# Rocky_Switch_Shield_v2.net
KiCad netlist of a schematic drawn in EAGLE
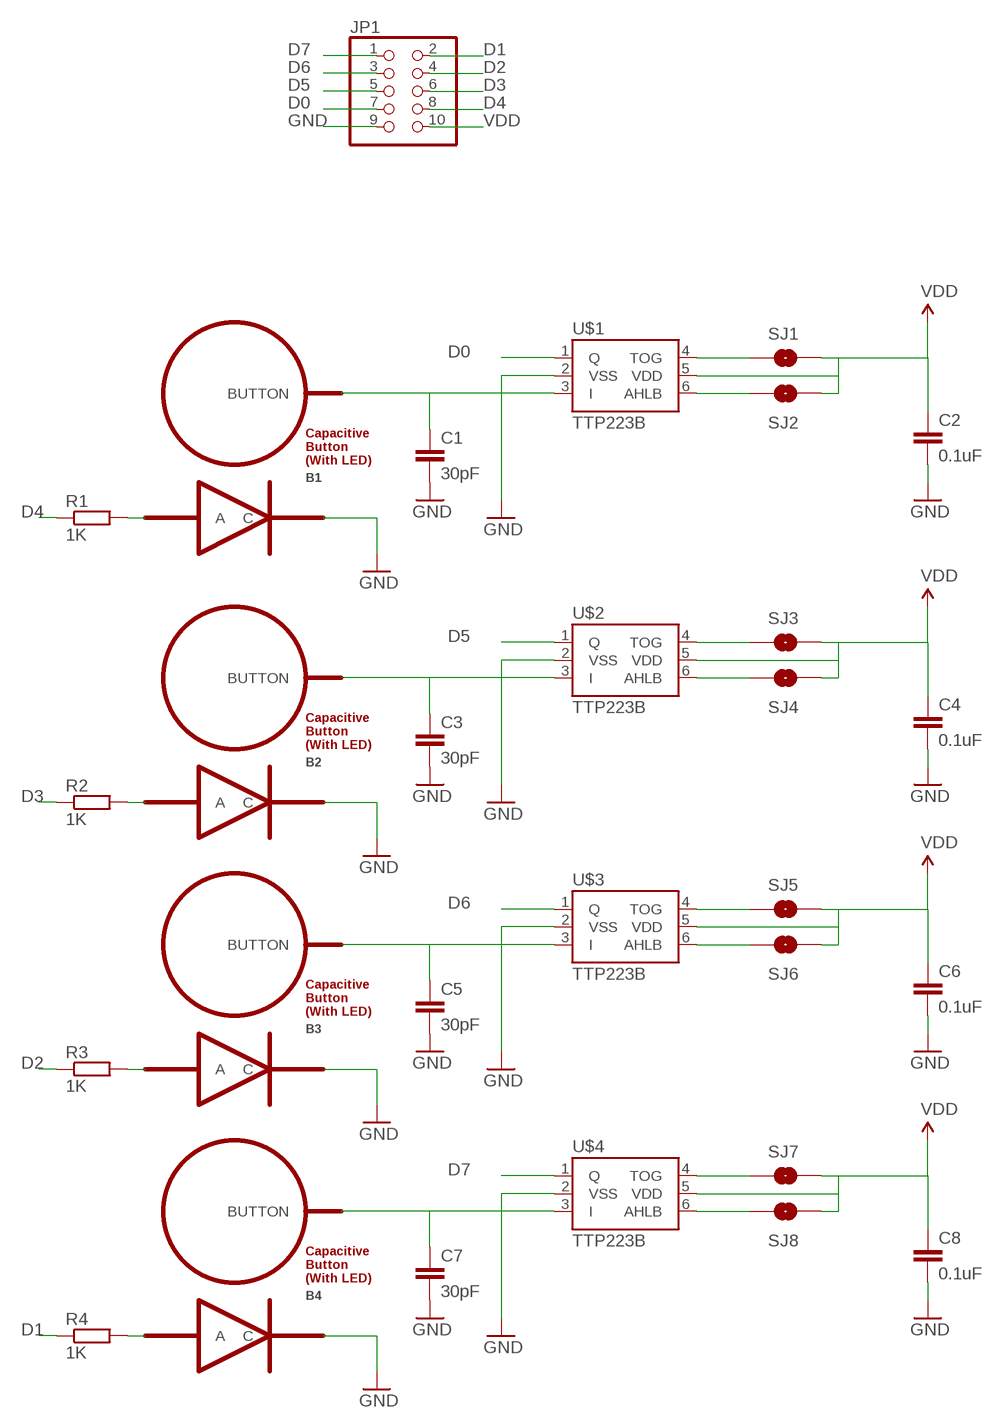
[diagram p0: schematic, sheet 1]

(export (version "E")
  (design (tool "Eeschema 10.0.6"))
  (components
    (comp (ref "B1")
      (value "BUTTON_PASSIVE_LED")
      (footprint "eagle-import:BUTTON_PASSIVE_12MM_LED")
      (libsource (lib "eagle-import") (part "BUTTON_PASSIVE_LED"))
    )
    (comp (ref "B2")
      (value "BUTTON_PASSIVE_LED")
      (footprint "eagle-import:BUTTON_PASSIVE_12MM_LED")
      (libsource (lib "eagle-import") (part "BUTTON_PASSIVE_LED"))
    )
    (comp (ref "B3")
      (value "BUTTON_PASSIVE_LED")
      (footprint "eagle-import:BUTTON_PASSIVE_12MM_LED")
      (libsource (lib "eagle-import") (part "BUTTON_PASSIVE_LED"))
    )
    (comp (ref "B4")
      (value "BUTTON_PASSIVE_LED")
      (footprint "eagle-import:BUTTON_PASSIVE_12MM_LED")
      (libsource (lib "eagle-import") (part "BUTTON_PASSIVE_LED"))
    )
    (comp (ref "C1")
      (value "30pF")
      (footprint "eagle-import:C0805K")
      (libsource (lib "eagle-import") (part "C-EUC0805K"))
    )
    (comp (ref "C2")
      (value "0.1uF")
      (footprint "eagle-import:C0805K")
      (libsource (lib "eagle-import") (part "C-EUC0805K"))
    )
    (comp (ref "C3")
      (value "30pF")
      (footprint "eagle-import:C0805K")
      (libsource (lib "eagle-import") (part "C-EUC0805K"))
    )
    (comp (ref "C4")
      (value "0.1uF")
      (footprint "eagle-import:C0805K")
      (libsource (lib "eagle-import") (part "C-EUC0805K"))
    )
    (comp (ref "C5")
      (value "30pF")
      (footprint "eagle-import:C0805K")
      (libsource (lib "eagle-import") (part "C-EUC0805K"))
    )
    (comp (ref "C6")
      (value "0.1uF")
      (footprint "eagle-import:C0805K")
      (libsource (lib "eagle-import") (part "C-EUC0805K"))
    )
    (comp (ref "C7")
      (value "30pF")
      (footprint "eagle-import:C0805K")
      (libsource (lib "eagle-import") (part "C-EUC0805K"))
    )
    (comp (ref "C8")
      (value "0.1uF")
      (footprint "eagle-import:C0805K")
      (libsource (lib "eagle-import") (part "C-EUC0805K"))
    )
    (comp (ref "JP1")
      (value "PINHD-2X5")
      (footprint "eagle-import:2X05")
      (libsource (lib "eagle-import") (part "PINHD-2X5"))
    )
    (comp (ref "R1")
      (value "1K")
      (footprint "eagle-import:R0805")
      (libsource (lib "eagle-import") (part "R-EU_R0805"))
    )
    (comp (ref "R2")
      (value "1K")
      (footprint "eagle-import:R0805")
      (libsource (lib "eagle-import") (part "R-EU_R0805"))
    )
    (comp (ref "R3")
      (value "1K")
      (footprint "eagle-import:R0805")
      (libsource (lib "eagle-import") (part "R-EU_R0805"))
    )
    (comp (ref "R4")
      (value "1K")
      (footprint "eagle-import:R0805")
      (libsource (lib "eagle-import") (part "R-EU_R0805"))
    )
    (comp (ref "SJ1")
      (value "JUMPER-PAD-2-NOYES_SILK")
      (footprint "eagle-import:PAD-JUMPER-2-NO_YES_SILK")
      (libsource (lib "eagle-import") (part "JUMPER-PAD-2-NOYES_SILK"))
    )
    (comp (ref "SJ2")
      (value "JUMPER-PAD-2-NOYES_SILK")
      (footprint "eagle-import:PAD-JUMPER-2-NO_YES_SILK")
      (libsource (lib "eagle-import") (part "JUMPER-PAD-2-NOYES_SILK"))
    )
    (comp (ref "SJ3")
      (value "JUMPER-PAD-2-NOYES_SILK")
      (footprint "eagle-import:PAD-JUMPER-2-NO_YES_SILK")
      (libsource (lib "eagle-import") (part "JUMPER-PAD-2-NOYES_SILK"))
    )
    (comp (ref "SJ4")
      (value "JUMPER-PAD-2-NOYES_SILK")
      (footprint "eagle-import:PAD-JUMPER-2-NO_YES_SILK")
      (libsource (lib "eagle-import") (part "JUMPER-PAD-2-NOYES_SILK"))
    )
    (comp (ref "SJ5")
      (value "JUMPER-PAD-2-NOYES_SILK")
      (footprint "eagle-import:PAD-JUMPER-2-NO_YES_SILK")
      (libsource (lib "eagle-import") (part "JUMPER-PAD-2-NOYES_SILK"))
    )
    (comp (ref "SJ6")
      (value "JUMPER-PAD-2-NOYES_SILK")
      (footprint "eagle-import:PAD-JUMPER-2-NO_YES_SILK")
      (libsource (lib "eagle-import") (part "JUMPER-PAD-2-NOYES_SILK"))
    )
    (comp (ref "SJ7")
      (value "JUMPER-PAD-2-NOYES_SILK")
      (footprint "eagle-import:PAD-JUMPER-2-NO_YES_SILK")
      (libsource (lib "eagle-import") (part "JUMPER-PAD-2-NOYES_SILK"))
    )
    (comp (ref "SJ8")
      (value "JUMPER-PAD-2-NOYES_SILK")
      (footprint "eagle-import:PAD-JUMPER-2-NO_YES_SILK")
      (libsource (lib "eagle-import") (part "JUMPER-PAD-2-NOYES_SILK"))
    )
    (comp (ref "U$1")
      (value "TTP223B")
      (footprint "eagle-import:SOT23-6")
      (libsource (lib "eagle-import") (part "TTP223B"))
    )
    (comp (ref "U$2")
      (value "TTP223B")
      (footprint "eagle-import:SOT23-6")
      (libsource (lib "eagle-import") (part "TTP223B"))
    )
    (comp (ref "U$3")
      (value "TTP223B")
      (footprint "eagle-import:SOT23-6")
      (libsource (lib "eagle-import") (part "TTP223B"))
    )
    (comp (ref "U$4")
      (value "TTP223B")
      (footprint "eagle-import:SOT23-6")
      (libsource (lib "eagle-import") (part "TTP223B"))
    )
  )
  (nets
    (net (code "1") (name "/D0") (class "Default")
      (node (ref "JP1") (pin "7") (pinfunction "7_7") (pintype "passive"))
      (node (ref "U$1") (pin "1") (pinfunction "Q_1") (pintype "bidirectional"))
    )
    (net (code "2") (name "/D1") (class "Default")
      (node (ref "JP1") (pin "2") (pinfunction "2_2") (pintype "passive"))
      (node (ref "R4") (pin "1") (pinfunction "1_1") (pintype "passive"))
    )
    (net (code "3") (name "/D2") (class "Default")
      (node (ref "JP1") (pin "4") (pinfunction "4_4") (pintype "passive"))
      (node (ref "R3") (pin "1") (pinfunction "1_1") (pintype "passive"))
    )
    (net (code "4") (name "/D3") (class "Default")
      (node (ref "JP1") (pin "6") (pinfunction "6_6") (pintype "passive"))
      (node (ref "R2") (pin "1") (pinfunction "1_1") (pintype "passive"))
    )
    (net (code "5") (name "/D4") (class "Default")
      (node (ref "JP1") (pin "8") (pinfunction "8_8") (pintype "passive"))
      (node (ref "R1") (pin "1") (pinfunction "1_1") (pintype "passive"))
    )
    (net (code "6") (name "/D5") (class "Default")
      (node (ref "JP1") (pin "5") (pinfunction "5_5") (pintype "passive"))
      (node (ref "U$2") (pin "1") (pinfunction "Q_1") (pintype "bidirectional"))
    )
    (net (code "7") (name "/D6") (class "Default")
      (node (ref "JP1") (pin "3") (pinfunction "3_3") (pintype "passive"))
      (node (ref "U$3") (pin "1") (pinfunction "Q_1") (pintype "bidirectional"))
    )
    (net (code "8") (name "/D7") (class "Default")
      (node (ref "JP1") (pin "1") (pinfunction "1_1") (pintype "passive"))
      (node (ref "U$4") (pin "1") (pinfunction "Q_1") (pintype "bidirectional"))
    )
    (net (code "9") (name "GND") (class "Default")
      (node (ref "B1") (pin "C") (pinfunction "C_C") (pintype "bidirectional"))
      (node (ref "B2") (pin "C") (pinfunction "C_C") (pintype "bidirectional"))
      (node (ref "B3") (pin "C") (pinfunction "C_C") (pintype "bidirectional"))
      (node (ref "B4") (pin "C") (pinfunction "C_C") (pintype "bidirectional"))
      (node (ref "C1") (pin "2") (pinfunction "2_2") (pintype "passive"))
      (node (ref "C2") (pin "2") (pinfunction "2_2") (pintype "passive"))
      (node (ref "C3") (pin "2") (pinfunction "2_2") (pintype "passive"))
      (node (ref "C4") (pin "2") (pinfunction "2_2") (pintype "passive"))
      (node (ref "C5") (pin "2") (pinfunction "2_2") (pintype "passive"))
      (node (ref "C6") (pin "2") (pinfunction "2_2") (pintype "passive"))
      (node (ref "C7") (pin "2") (pinfunction "2_2") (pintype "passive"))
      (node (ref "C8") (pin "2") (pinfunction "2_2") (pintype "passive"))
      (node (ref "JP1") (pin "9") (pinfunction "9_9") (pintype "passive"))
      (node (ref "U$1") (pin "2") (pinfunction "VSS_2") (pintype "bidirectional"))
      (node (ref "U$2") (pin "2") (pinfunction "VSS_2") (pintype "bidirectional"))
      (node (ref "U$3") (pin "2") (pinfunction "VSS_2") (pintype "bidirectional"))
      (node (ref "U$4") (pin "2") (pinfunction "VSS_2") (pintype "bidirectional"))
    )
    (net (code "10") (name "Net-(B1-PadA)") (class "Default")
      (node (ref "B1") (pin "A") (pinfunction "A_A") (pintype "bidirectional"))
      (node (ref "R1") (pin "2") (pinfunction "2_2") (pintype "passive"))
    )
    (net (code "11") (name "Net-(B2-PadA)") (class "Default")
      (node (ref "B2") (pin "A") (pinfunction "A_A") (pintype "bidirectional"))
      (node (ref "R2") (pin "2") (pinfunction "2_2") (pintype "passive"))
    )
    (net (code "12") (name "Net-(B3-PadA)") (class "Default")
      (node (ref "B3") (pin "A") (pinfunction "A_A") (pintype "bidirectional"))
      (node (ref "R3") (pin "2") (pinfunction "2_2") (pintype "passive"))
    )
    (net (code "13") (name "Net-(B4-PadA)") (class "Default")
      (node (ref "B4") (pin "A") (pinfunction "A_A") (pintype "bidirectional"))
      (node (ref "R4") (pin "2") (pinfunction "2_2") (pintype "passive"))
    )
    (net (code "14") (name "Net-(U$1-AHLB)") (class "Default")
      (node (ref "SJ2") (pin "1") (pinfunction "1_1") (pintype "passive"))
      (node (ref "U$1") (pin "6") (pinfunction "AHLB_6") (pintype "bidirectional"))
    )
    (net (code "15") (name "Net-(U$1-I)") (class "Default")
      (node (ref "B1") (pin "BUTTON") (pinfunction "BUTTON_BUTTON") (pintype "passive"))
      (node (ref "C1") (pin "1") (pinfunction "1_1") (pintype "passive"))
      (node (ref "U$1") (pin "3") (pinfunction "I_3") (pintype "bidirectional"))
    )
    (net (code "16") (name "Net-(U$1-TOG)") (class "Default")
      (node (ref "SJ1") (pin "1") (pinfunction "1_1") (pintype "passive"))
      (node (ref "U$1") (pin "4") (pinfunction "TOG_4") (pintype "bidirectional"))
    )
    (net (code "17") (name "Net-(U$2-AHLB)") (class "Default")
      (node (ref "SJ4") (pin "1") (pinfunction "1_1") (pintype "passive"))
      (node (ref "U$2") (pin "6") (pinfunction "AHLB_6") (pintype "bidirectional"))
    )
    (net (code "18") (name "Net-(U$2-I)") (class "Default")
      (node (ref "B2") (pin "BUTTON") (pinfunction "BUTTON_BUTTON") (pintype "passive"))
      (node (ref "C3") (pin "1") (pinfunction "1_1") (pintype "passive"))
      (node (ref "U$2") (pin "3") (pinfunction "I_3") (pintype "bidirectional"))
    )
    (net (code "19") (name "Net-(U$2-TOG)") (class "Default")
      (node (ref "SJ3") (pin "1") (pinfunction "1_1") (pintype "passive"))
      (node (ref "U$2") (pin "4") (pinfunction "TOG_4") (pintype "bidirectional"))
    )
    (net (code "20") (name "Net-(U$3-AHLB)") (class "Default")
      (node (ref "SJ6") (pin "1") (pinfunction "1_1") (pintype "passive"))
      (node (ref "U$3") (pin "6") (pinfunction "AHLB_6") (pintype "bidirectional"))
    )
    (net (code "21") (name "Net-(U$3-I)") (class "Default")
      (node (ref "B3") (pin "BUTTON") (pinfunction "BUTTON_BUTTON") (pintype "passive"))
      (node (ref "C5") (pin "1") (pinfunction "1_1") (pintype "passive"))
      (node (ref "U$3") (pin "3") (pinfunction "I_3") (pintype "bidirectional"))
    )
    (net (code "22") (name "Net-(U$3-TOG)") (class "Default")
      (node (ref "SJ5") (pin "1") (pinfunction "1_1") (pintype "passive"))
      (node (ref "U$3") (pin "4") (pinfunction "TOG_4") (pintype "bidirectional"))
    )
    (net (code "23") (name "Net-(U$4-AHLB)") (class "Default")
      (node (ref "SJ8") (pin "1") (pinfunction "1_1") (pintype "passive"))
      (node (ref "U$4") (pin "6") (pinfunction "AHLB_6") (pintype "bidirectional"))
    )
    (net (code "24") (name "Net-(U$4-I)") (class "Default")
      (node (ref "B4") (pin "BUTTON") (pinfunction "BUTTON_BUTTON") (pintype "passive"))
      (node (ref "C7") (pin "1") (pinfunction "1_1") (pintype "passive"))
      (node (ref "U$4") (pin "3") (pinfunction "I_3") (pintype "bidirectional"))
    )
    (net (code "25") (name "Net-(U$4-TOG)") (class "Default")
      (node (ref "SJ7") (pin "1") (pinfunction "1_1") (pintype "passive"))
      (node (ref "U$4") (pin "4") (pinfunction "TOG_4") (pintype "bidirectional"))
    )
    (net (code "26") (name "VDD") (class "Default")
      (node (ref "C2") (pin "1") (pinfunction "1_1") (pintype "passive"))
      (node (ref "C4") (pin "1") (pinfunction "1_1") (pintype "passive"))
      (node (ref "C6") (pin "1") (pinfunction "1_1") (pintype "passive"))
      (node (ref "C8") (pin "1") (pinfunction "1_1") (pintype "passive"))
      (node (ref "JP1") (pin "10") (pinfunction "10_10") (pintype "passive"))
      (node (ref "SJ1") (pin "2") (pinfunction "2_2") (pintype "passive"))
      (node (ref "SJ2") (pin "2") (pinfunction "2_2") (pintype "passive"))
      (node (ref "SJ3") (pin "2") (pinfunction "2_2") (pintype "passive"))
      (node (ref "SJ4") (pin "2") (pinfunction "2_2") (pintype "passive"))
      (node (ref "SJ5") (pin "2") (pinfunction "2_2") (pintype "passive"))
      (node (ref "SJ6") (pin "2") (pinfunction "2_2") (pintype "passive"))
      (node (ref "SJ7") (pin "2") (pinfunction "2_2") (pintype "passive"))
      (node (ref "SJ8") (pin "2") (pinfunction "2_2") (pintype "passive"))
      (node (ref "U$1") (pin "5") (pinfunction "VDD_5") (pintype "bidirectional"))
      (node (ref "U$2") (pin "5") (pinfunction "VDD_5") (pintype "bidirectional"))
      (node (ref "U$3") (pin "5") (pinfunction "VDD_5") (pintype "bidirectional"))
      (node (ref "U$4") (pin "5") (pinfunction "VDD_5") (pintype "bidirectional"))
    )
  )
)
